# Bio_v4_LCD1_0.net
KiCad netlist of a schematic drawn in EAGLE
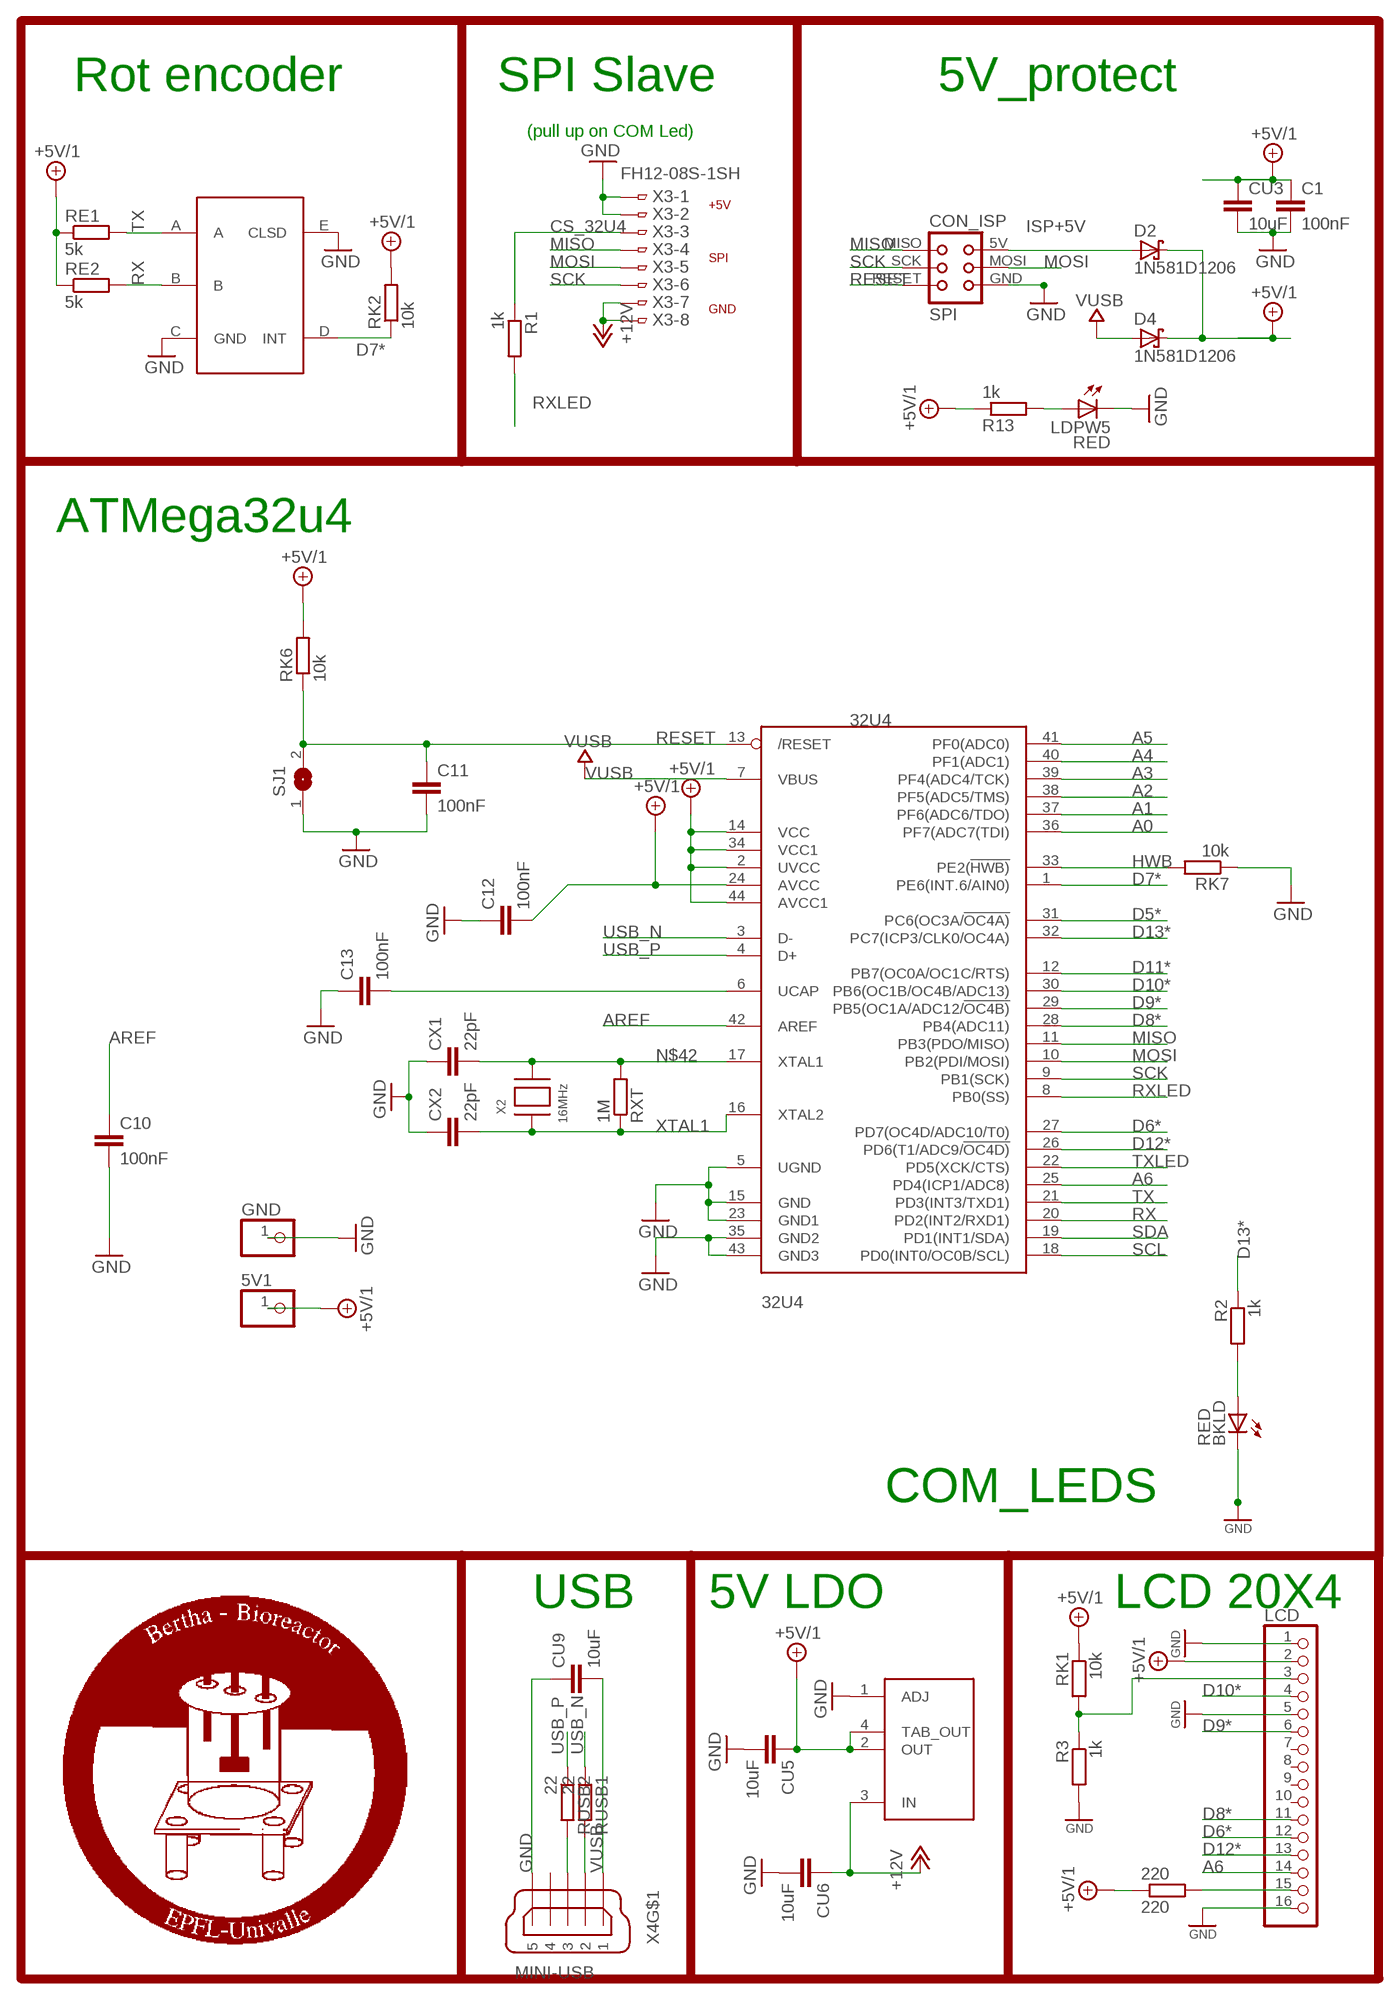
[diagram p0: schematic, sheet 1]

(export (version "E")
  (design (tool "Eeschema 10.0.6"))
  (components
    (comp (ref "5V1")
      (value "PINHD-1X1")
      (footprint "eagle-import:1X01")
      (libsource (lib "eagle-import") (part "PINHD-1X1"))
    )
    (comp (ref "32U4")
      (value "32U4")
      (footprint "eagle-import:TQFP44")
      (libsource (lib "eagle-import") (part "ATMEGA32U4-AU"))
    )
    (comp (ref "220")
      (value "220")
      (footprint "eagle-import:R0805")
      (libsource (lib "eagle-import") (part "R-EU_R0805"))
    )
    (comp (ref "BKLD")
      (value "RED")
      (footprint "eagle-import:CHIP-LED0805")
      (libsource (lib "eagle-import") (part "LEDCHIP-LED0805"))
    )
    (comp (ref "C1")
      (value "100nF")
      (footprint "eagle-import:C1206")
      (libsource (lib "eagle-import") (part "C-EUC1206"))
    )
    (comp (ref "C10")
      (value "100nF")
      (footprint "eagle-import:C1206")
      (libsource (lib "eagle-import") (part "C-EUC1206"))
    )
    (comp (ref "C11")
      (value "100nF")
      (footprint "eagle-import:C1206")
      (libsource (lib "eagle-import") (part "C-EUC1206"))
    )
    (comp (ref "C12")
      (value "100nF")
      (footprint "eagle-import:C1206")
      (libsource (lib "eagle-import") (part "C-EUC1206"))
    )
    (comp (ref "C13")
      (value "100nF")
      (footprint "eagle-import:C1206")
      (libsource (lib "eagle-import") (part "C-EUC1206"))
    )
    (comp (ref "CON_ISP")
      (value "SPI")
      (footprint "eagle-import:TC2030-MCP-NL")
      (libsource (lib "eagle-import") (part "TINYISPT"))
    )
    (comp (ref "CU3")
      (value "10uF")
      (footprint "eagle-import:C1206")
      (libsource (lib "eagle-import") (part "C-EUC1206"))
    )
    (comp (ref "CU5")
      (value "10uF")
      (footprint "eagle-import:C1206")
      (libsource (lib "eagle-import") (part "C-EUC1206"))
    )
    (comp (ref "CU6")
      (value "10uF")
      (footprint "eagle-import:C1206")
      (libsource (lib "eagle-import") (part "C-EUC1206"))
    )
    (comp (ref "CU9")
      (value "10uF")
      (footprint "eagle-import:C1206")
      (libsource (lib "eagle-import") (part "C-EUC1206"))
    )
    (comp (ref "CX1")
      (value "22pF")
      (footprint "eagle-import:C1206")
      (libsource (lib "eagle-import") (part "C-EUC1206"))
    )
    (comp (ref "CX2")
      (value "22pF")
      (footprint "eagle-import:C1206")
      (libsource (lib "eagle-import") (part "C-EUC1206"))
    )
    (comp (ref "D2")
      (value "1N581D1206")
      (footprint "eagle-import:LED-1206")
      (libsource (lib "eagle-import") (part "1N581D1206"))
    )
    (comp (ref "D4")
      (value "1N581D1206")
      (footprint "eagle-import:LED-1206")
      (libsource (lib "eagle-import") (part "1N581D1206"))
    )
    (comp (ref "GND")
      (value "PINHD-1X1")
      (footprint "eagle-import:1X01")
      (libsource (lib "eagle-import") (part "PINHD-1X1"))
    )
    (comp (ref "LCD")
      (value "LCD-HEADER")
      (footprint "eagle-import:1X16")
      (libsource (lib "eagle-import") (part "LCD-HEADER"))
    )
    (comp (ref "LDO")
      (value "NCP1117LPST50T3G")
      (footprint "eagle-import:SOT223")
      (libsource (lib "eagle-import") (part "NCP1117LPST50T3G"))
    )
    (comp (ref "LDPW5")
      (value "RED")
      (footprint "eagle-import:CHIP-LED0805")
      (libsource (lib "eagle-import") (part "LEDCHIP-LED0805"))
    )
    (comp (ref "R1")
      (value "1k")
      (footprint "eagle-import:R0805")
      (libsource (lib "eagle-import") (part "R-EU_R0805"))
    )
    (comp (ref "R2")
      (value "1k")
      (footprint "eagle-import:R0805")
      (libsource (lib "eagle-import") (part "R-EU_R0805"))
    )
    (comp (ref "R3")
      (value "1k")
      (footprint "eagle-import:R0805")
      (libsource (lib "eagle-import") (part "R-EU_R0805"))
    )
    (comp (ref "R13")
      (value "1k")
      (footprint "eagle-import:R0805")
      (libsource (lib "eagle-import") (part "resistor_R-EU_R0805"))
    )
    (comp (ref "RE1")
      (value "5k")
      (footprint "eagle-import:R0805")
      (libsource (lib "eagle-import") (part "R-EU_R0805"))
    )
    (comp (ref "RE2")
      (value "5k")
      (footprint "eagle-import:R0805")
      (libsource (lib "eagle-import") (part "R-EU_R0805"))
    )
    (comp (ref "RK1")
      (value "10k")
      (footprint "eagle-import:R0805")
      (libsource (lib "eagle-import") (part "R-EU_R0805"))
    )
    (comp (ref "RK2")
      (value "10k")
      (footprint "eagle-import:M0805")
      (libsource (lib "eagle-import") (part "resistor_R-EU_M0805"))
    )
    (comp (ref "RK6")
      (value "10k")
      (footprint "eagle-import:M0805")
      (libsource (lib "eagle-import") (part "resistor_R-EU_M0805"))
    )
    (comp (ref "RK7")
      (value "10k")
      (footprint "eagle-import:M0805")
      (libsource (lib "eagle-import") (part "resistor_R-EU_M0805"))
    )
    (comp (ref "RUSB1")
      (value "22")
      (footprint "eagle-import:M1206")
      (libsource (lib "eagle-import") (part "resistor_R-EU_M1206"))
    )
    (comp (ref "RUSB2")
      (value "22")
      (footprint "eagle-import:M1206")
      (libsource (lib "eagle-import") (part "resistor_R-EU_M1206"))
    )
    (comp (ref "RXT")
      (value "1M")
      (footprint "eagle-import:R0805")
      (libsource (lib "eagle-import") (part "R-EU_R0805"))
    )
    (comp (ref "SJ1") (value "SJ") (footprint "eagle-import:SJ") (libsource (lib "eagle-import") (part "SJ")))
    (comp (ref "U$1")
      (value "EC11E")
      (footprint "eagle-import:EC11E")
      (libsource (lib "eagle-import") (part "EC11E"))
    )
    (comp (ref "X2")
      (value "16MHz")
      (footprint "eagle-import:NX6035")
      (libsource (lib "eagle-import") (part "XTALNX6035"))
    )
    (comp (ref "X3")
      (value "FH12-08S-1SH")
      (footprint "eagle-import:FH12-08S-1SH")
      (libsource (lib "eagle-import") (part "FH12-08S-1SH"))
    )
    (comp (ref "X4")
      (value "MINI-USB")
      (footprint "eagle-import:32005-201")
      (libsource (lib "eagle-import") (part "MINI-USB-SCHIELD-32005-201"))
    )
  )
  (nets
    (net (code "1") (name "+5V{slash}1") (class "Default")
      (node (ref "220") (pin "1") (pinfunction "1_1") (pintype "passive"))
      (node (ref "32U4") (pin "14") (pinfunction "VCC_14") (pintype "bidirectional"))
      (node (ref "32U4") (pin "2") (pinfunction "UVCC_2") (pintype "bidirectional"))
      (node (ref "32U4") (pin "24") (pinfunction "AVCC_24") (pintype "bidirectional"))
      (node (ref "32U4") (pin "34") (pinfunction "VCC1_34") (pintype "bidirectional"))
      (node (ref "32U4") (pin "44") (pinfunction "AVCC1_44") (pintype "bidirectional"))
      (node (ref "5V1") (pin "1") (pinfunction "1_1") (pintype "passive"))
      (node (ref "C1") (pin "1") (pinfunction "1_1") (pintype "passive"))
      (node (ref "C12") (pin "2") (pinfunction "2_2") (pintype "passive"))
      (node (ref "CU3") (pin "1") (pinfunction "1_1") (pintype "passive"))
      (node (ref "CU5") (pin "1") (pinfunction "1_1") (pintype "passive"))
      (node (ref "D2") (pin "C") (pinfunction "C_C") (pintype "passive"))
      (node (ref "D4") (pin "C") (pinfunction "C_C") (pintype "passive"))
      (node (ref "LCD") (pin "2") (pinfunction "2_2") (pintype "passive"))
      (node (ref "LDO") (pin "2") (pinfunction "OUT_2") (pintype "bidirectional"))
      (node (ref "LDO") (pin "4") (pinfunction "TAB_OUT_4") (pintype "bidirectional"))
      (node (ref "R13") (pin "1") (pinfunction "1_1") (pintype "passive"))
      (node (ref "RE1") (pin "1") (pinfunction "1_1") (pintype "passive"))
      (node (ref "RE2") (pin "1") (pinfunction "1_1") (pintype "passive"))
      (node (ref "RK1") (pin "1") (pinfunction "1_1") (pintype "passive"))
      (node (ref "RK2") (pin "2") (pinfunction "2_2") (pintype "passive"))
      (node (ref "RK6") (pin "2") (pinfunction "2_2") (pintype "passive"))
    )
    (net (code "2") (name "+12V") (class "Default")
      (node (ref "CU6") (pin "1") (pinfunction "1_1") (pintype "passive"))
      (node (ref "LDO") (pin "3") (pinfunction "IN_3") (pintype "bidirectional"))
      (node (ref "X3") (pin "7") (pinfunction "1_7") (pintype "passive"))
      (node (ref "X3") (pin "8") (pinfunction "1_8") (pintype "passive"))
    )
    (net (code "3") (name "/A0") (class "Default")
      (node (ref "32U4") (pin "36") (pinfunction "PF7(ADC7(TDI)_36") (pintype "bidirectional"))
    )
    (net (code "4") (name "/A1") (class "Default")
      (node (ref "32U4") (pin "37") (pinfunction "PF6(ADC6/TDO)_37") (pintype "bidirectional"))
    )
    (net (code "5") (name "/A2") (class "Default")
      (node (ref "32U4") (pin "38") (pinfunction "PF5(ADC5/TMS)_38") (pintype "bidirectional"))
    )
    (net (code "6") (name "/A3") (class "Default")
      (node (ref "32U4") (pin "39") (pinfunction "PF4(ADC4/TCK)_39") (pintype "bidirectional"))
    )
    (net (code "7") (name "/A4") (class "Default")
      (node (ref "32U4") (pin "40") (pinfunction "PF1(ADC1)_40") (pintype "bidirectional"))
    )
    (net (code "8") (name "/A5") (class "Default")
      (node (ref "32U4") (pin "41") (pinfunction "PF0(ADC0)_41") (pintype "bidirectional"))
    )
    (net (code "9") (name "/A6") (class "Default")
      (node (ref "32U4") (pin "25") (pinfunction "PD4(ICP1/ADC8)_25") (pintype "bidirectional"))
      (node (ref "LCD") (pin "14") (pinfunction "14_14") (pintype "passive"))
    )
    (net (code "10") (name "/AREF") (class "Default")
      (node (ref "32U4") (pin "42") (pinfunction "AREF_42") (pintype "bidirectional"))
      (node (ref "C10") (pin "1") (pinfunction "1_1") (pintype "passive"))
    )
    (net (code "11") (name "/CS_32U4") (class "Default")
      (node (ref "R1") (pin "1") (pinfunction "1_1") (pintype "passive"))
      (node (ref "X3") (pin "3") (pinfunction "1_3") (pintype "passive"))
    )
    (net (code "12") (name "/D5*") (class "Default")
      (node (ref "32U4") (pin "31") (pinfunction "PC6(OC3A/~{OC4A})_31") (pintype "bidirectional"))
    )
    (net (code "13") (name "/D6*") (class "Default")
      (node (ref "32U4") (pin "27") (pinfunction "PD7(OC4D/ADC10/T0)_27") (pintype "bidirectional"))
      (node (ref "LCD") (pin "12") (pinfunction "12_12") (pintype "passive"))
    )
    (net (code "14") (name "/D7*") (class "Default")
      (node (ref "32U4") (pin "1") (pinfunction "PE6(INT.6/AIN0)_1") (pintype "bidirectional"))
      (node (ref "RK2") (pin "1") (pinfunction "1_1") (pintype "passive"))
      (node (ref "U$1") (pin "D") (pinfunction "INT_D") (pintype "bidirectional"))
    )
    (net (code "15") (name "/D8*") (class "Default")
      (node (ref "32U4") (pin "28") (pinfunction "PB4(ADC11)_28") (pintype "bidirectional"))
      (node (ref "LCD") (pin "11") (pinfunction "11_11") (pintype "passive"))
    )
    (net (code "16") (name "/D9*") (class "Default")
      (node (ref "32U4") (pin "29") (pinfunction "PB5(OC1A/ADC12/~{OC4B})_29") (pintype "bidirectional"))
      (node (ref "LCD") (pin "6") (pinfunction "6_6") (pintype "passive"))
    )
    (net (code "17") (name "/D10*") (class "Default")
      (node (ref "32U4") (pin "30") (pinfunction "PB6(OC1B/OC4B/ADC13)_30") (pintype "bidirectional"))
      (node (ref "LCD") (pin "4") (pinfunction "4_4") (pintype "passive"))
    )
    (net (code "18") (name "/D11*") (class "Default")
      (node (ref "32U4") (pin "12") (pinfunction "PB7(OC0A/OC1C/RTS)_12") (pintype "bidirectional"))
    )
    (net (code "19") (name "/D12*") (class "Default")
      (node (ref "32U4") (pin "26") (pinfunction "PD6(T1/ADC9/~{OC4D})_26") (pintype "bidirectional"))
      (node (ref "LCD") (pin "13") (pinfunction "13_13") (pintype "passive"))
    )
    (net (code "20") (name "/D13*") (class "Default")
      (node (ref "32U4") (pin "32") (pinfunction "PC7(ICP3/CLK0/OC4A)_32") (pintype "bidirectional"))
      (node (ref "R2") (pin "1") (pinfunction "1_1") (pintype "passive"))
    )
    (net (code "21") (name "/HWB") (class "Default")
      (node (ref "32U4") (pin "33") (pinfunction "PE2(~{HWB})_33") (pintype "bidirectional"))
      (node (ref "RK7") (pin "2") (pinfunction "2_2") (pintype "passive"))
    )
    (net (code "22") (name "/ISP+5V") (class "Default")
      (node (ref "CON_ISP") (pin "5V") (pinfunction "VCC_5V") (pintype "passive"))
      (node (ref "D2") (pin "A") (pinfunction "A_A") (pintype "passive"))
    )
    (net (code "23") (name "/MISO") (class "Default")
      (node (ref "32U4") (pin "11") (pinfunction "PB3(PDO/MISO)_11") (pintype "bidirectional"))
      (node (ref "CON_ISP") (pin "MISO") (pinfunction "MISO_MISO") (pintype "passive"))
      (node (ref "X3") (pin "4") (pinfunction "1_4") (pintype "passive"))
    )
    (net (code "24") (name "/MOSI") (class "Default")
      (node (ref "32U4") (pin "10") (pinfunction "PB2(PDI/MOSI)_10") (pintype "bidirectional"))
      (node (ref "CON_ISP") (pin "MOSI") (pinfunction "MOSI_MOSI") (pintype "passive"))
      (node (ref "X3") (pin "5") (pinfunction "1_5") (pintype "passive"))
    )
    (net (code "25") (name "/N$42") (class "Default")
      (node (ref "32U4") (pin "17") (pinfunction "XTAL1_17") (pintype "bidirectional"))
      (node (ref "CX1") (pin "2") (pinfunction "2_2") (pintype "passive"))
      (node (ref "RXT") (pin "2") (pinfunction "2_2") (pintype "passive"))
      (node (ref "X2") (pin "P$2") (pinfunction "P$2_P$2") (pintype "bidirectional"))
    )
    (net (code "26") (name "/RESET") (class "Default")
      (node (ref "32U4") (pin "13") (pinfunction "/RESET_13") (pintype "bidirectional"))
      (node (ref "C11") (pin "1") (pinfunction "1_1") (pintype "passive"))
      (node (ref "CON_ISP") (pin "RESET") (pinfunction "RESET_RESET") (pintype "passive"))
      (node (ref "RK6") (pin "1") (pinfunction "1_1") (pintype "passive"))
      (node (ref "SJ1") (pin "2") (pinfunction "2_2") (pintype "passive"))
    )
    (net (code "27") (name "/RX") (class "Default")
      (node (ref "32U4") (pin "20") (pinfunction "PD2(INT2/RXD1)_20") (pintype "bidirectional"))
      (node (ref "RE2") (pin "2") (pinfunction "2_2") (pintype "passive"))
      (node (ref "U$1") (pin "B") (pinfunction "B_B") (pintype "bidirectional"))
    )
    (net (code "28") (name "/RXLED") (class "Default")
      (node (ref "32U4") (pin "8") (pinfunction "PB0(SS)_8") (pintype "bidirectional"))
      (node (ref "R1") (pin "2") (pinfunction "2_2") (pintype "passive"))
    )
    (net (code "29") (name "/SCK") (class "Default")
      (node (ref "32U4") (pin "9") (pinfunction "PB1(SCK)_9") (pintype "bidirectional"))
      (node (ref "CON_ISP") (pin "SCK") (pinfunction "SCK_SCK") (pintype "passive"))
      (node (ref "X3") (pin "6") (pinfunction "1_6") (pintype "passive"))
    )
    (net (code "30") (name "/SCL") (class "Default")
      (node (ref "32U4") (pin "18") (pinfunction "PD0(INT0/OC0B/SCL)_18") (pintype "bidirectional"))
    )
    (net (code "31") (name "/SDA") (class "Default")
      (node (ref "32U4") (pin "19") (pinfunction "PD1(INT1/SDA)_19") (pintype "bidirectional"))
    )
    (net (code "32") (name "/TX") (class "Default")
      (node (ref "32U4") (pin "21") (pinfunction "PD3(INT3/TXD1)_21") (pintype "bidirectional"))
      (node (ref "RE1") (pin "2") (pinfunction "2_2") (pintype "passive"))
      (node (ref "U$1") (pin "A") (pinfunction "A_A") (pintype "bidirectional"))
    )
    (net (code "33") (name "/TXLED") (class "Default")
      (node (ref "32U4") (pin "22") (pinfunction "PD5(XCK/CTS)_22") (pintype "bidirectional"))
    )
    (net (code "34") (name "/USB_N") (class "Default")
      (node (ref "32U4") (pin "3") (pinfunction "D-_3") (pintype "bidirectional"))
      (node (ref "RUSB1") (pin "1") (pinfunction "1_1") (pintype "passive"))
    )
    (net (code "35") (name "/USB_P") (class "Default")
      (node (ref "32U4") (pin "4") (pinfunction "D+_4") (pintype "bidirectional"))
      (node (ref "RUSB2") (pin "1") (pinfunction "1_1") (pintype "passive"))
    )
    (net (code "36") (name "/XTAL1") (class "Default")
      (node (ref "32U4") (pin "16") (pinfunction "XTAL2_16") (pintype "bidirectional"))
      (node (ref "CX2") (pin "2") (pinfunction "2_2") (pintype "passive"))
      (node (ref "RXT") (pin "1") (pinfunction "1_1") (pintype "passive"))
      (node (ref "X2") (pin "P$1") (pinfunction "P$1_P$1") (pintype "bidirectional"))
    )
    (net (code "37") (name "GND") (class "Default")
      (node (ref "32U4") (pin "15") (pinfunction "GND_15") (pintype "bidirectional"))
      (node (ref "32U4") (pin "23") (pinfunction "GND1_23") (pintype "bidirectional"))
      (node (ref "32U4") (pin "35") (pinfunction "GND2_35") (pintype "bidirectional"))
      (node (ref "32U4") (pin "43") (pinfunction "GND3_43") (pintype "bidirectional"))
      (node (ref "32U4") (pin "5") (pinfunction "UGND_5") (pintype "bidirectional"))
      (node (ref "BKLD") (pin "C") (pinfunction "C_C") (pintype "passive"))
      (node (ref "C1") (pin "2") (pinfunction "2_2") (pintype "passive"))
      (node (ref "C10") (pin "2") (pinfunction "2_2") (pintype "passive"))
      (node (ref "C11") (pin "2") (pinfunction "2_2") (pintype "passive"))
      (node (ref "C12") (pin "1") (pinfunction "1_1") (pintype "passive"))
      (node (ref "C13") (pin "1") (pinfunction "1_1") (pintype "passive"))
      (node (ref "CON_ISP") (pin "GND") (pinfunction "GND_GND") (pintype "passive"))
      (node (ref "CU3") (pin "2") (pinfunction "2_2") (pintype "passive"))
      (node (ref "CU5") (pin "2") (pinfunction "2_2") (pintype "passive"))
      (node (ref "CU6") (pin "2") (pinfunction "2_2") (pintype "passive"))
      (node (ref "CU9") (pin "1") (pinfunction "1_1") (pintype "passive"))
      (node (ref "CX1") (pin "1") (pinfunction "1_1") (pintype "passive"))
      (node (ref "CX2") (pin "1") (pinfunction "1_1") (pintype "passive"))
      (node (ref "GND") (pin "1") (pinfunction "1_1") (pintype "passive"))
      (node (ref "LCD") (pin "1") (pinfunction "1_1") (pintype "passive"))
      (node (ref "LCD") (pin "16") (pinfunction "16_16") (pintype "passive"))
      (node (ref "LCD") (pin "5") (pinfunction "5_5") (pintype "passive"))
      (node (ref "LDO") (pin "1") (pinfunction "ADJ_1") (pintype "bidirectional"))
      (node (ref "LDPW5") (pin "C") (pinfunction "C_C") (pintype "passive"))
      (node (ref "R3") (pin "2") (pinfunction "2_2") (pintype "passive"))
      (node (ref "RK7") (pin "1") (pinfunction "1_1") (pintype "passive"))
      (node (ref "SJ1") (pin "1") (pinfunction "1_1") (pintype "passive"))
      (node (ref "U$1") (pin "C") (pinfunction "GND_C") (pintype "bidirectional"))
      (node (ref "U$1") (pin "E") (pinfunction "CLSD_E") (pintype "bidirectional"))
      (node (ref "X3") (pin "1") (pinfunction "1_1") (pintype "passive"))
      (node (ref "X3") (pin "2") (pinfunction "1_2") (pintype "passive"))
      (node (ref "X4") (pin "5") (pinfunction "5_5") (pintype "passive"))
    )
    (net (code "38") (name "Net-(32U4-UCAP)") (class "Default")
      (node (ref "32U4") (pin "6") (pinfunction "UCAP_6") (pintype "bidirectional"))
      (node (ref "C13") (pin "2") (pinfunction "2_2") (pintype "passive"))
    )
    (net (code "39") (name "Net-(220-Pad2)") (class "Default")
      (node (ref "220") (pin "2") (pinfunction "2_2") (pintype "passive"))
      (node (ref "LCD") (pin "15") (pinfunction "15_15") (pintype "passive"))
    )
    (net (code "40") (name "Net-(BKLD-PadA)") (class "Default")
      (node (ref "BKLD") (pin "A") (pinfunction "A_A") (pintype "passive"))
      (node (ref "R2") (pin "2") (pinfunction "2_2") (pintype "passive"))
    )
    (net (code "41") (name "Net-(LCD-Pad3)") (class "Default")
      (node (ref "LCD") (pin "3") (pinfunction "3_3") (pintype "passive"))
      (node (ref "R3") (pin "1") (pinfunction "1_1") (pintype "passive"))
      (node (ref "RK1") (pin "2") (pinfunction "2_2") (pintype "passive"))
    )
    (net (code "42") (name "Net-(LDPW5-PadA)") (class "Default")
      (node (ref "LDPW5") (pin "A") (pinfunction "A_A") (pintype "passive"))
      (node (ref "R13") (pin "2") (pinfunction "2_2") (pintype "passive"))
    )
    (net (code "43") (name "Net-(RUSB1-Pad2)") (class "Default")
      (node (ref "RUSB1") (pin "2") (pinfunction "2_2") (pintype "passive"))
      (node (ref "X4") (pin "2") (pinfunction "2_2") (pintype "passive"))
    )
    (net (code "44") (name "Net-(RUSB2-Pad2)") (class "Default")
      (node (ref "RUSB2") (pin "2") (pinfunction "2_2") (pintype "passive"))
      (node (ref "X4") (pin "3") (pinfunction "3_3") (pintype "passive"))
    )
    (net (code "45") (name "VUSB") (class "Default")
      (node (ref "32U4") (pin "7") (pinfunction "VBUS_7") (pintype "bidirectional"))
      (node (ref "CU9") (pin "2") (pinfunction "2_2") (pintype "passive"))
      (node (ref "D4") (pin "A") (pinfunction "A_A") (pintype "passive"))
      (node (ref "X4") (pin "1") (pinfunction "1_1") (pintype "passive"))
    )
    (net (code "46") (name "unconnected-(LCD-Pad7)") (class "Default")
      (node (ref "LCD") (pin "7") (pinfunction "7_7") (pintype "passive"))
    )
    (net (code "47") (name "unconnected-(LCD-Pad8)") (class "Default")
      (node (ref "LCD") (pin "8") (pinfunction "8_8") (pintype "passive"))
    )
    (net (code "48") (name "unconnected-(LCD-Pad9)") (class "Default")
      (node (ref "LCD") (pin "9") (pinfunction "9_9") (pintype "passive"))
    )
    (net (code "49") (name "unconnected-(LCD-Pad10)") (class "Default")
      (node (ref "LCD") (pin "10") (pinfunction "10_10") (pintype "passive"))
    )
    (net (code "50") (name "unconnected-(X4-Pad4)") (class "Default")
      (node (ref "X4") (pin "4") (pinfunction "4_4") (pintype "passive"))
    )
  )
)
